# flossjtag.net
KiCad netlist of a schematic drawn in EAGLE
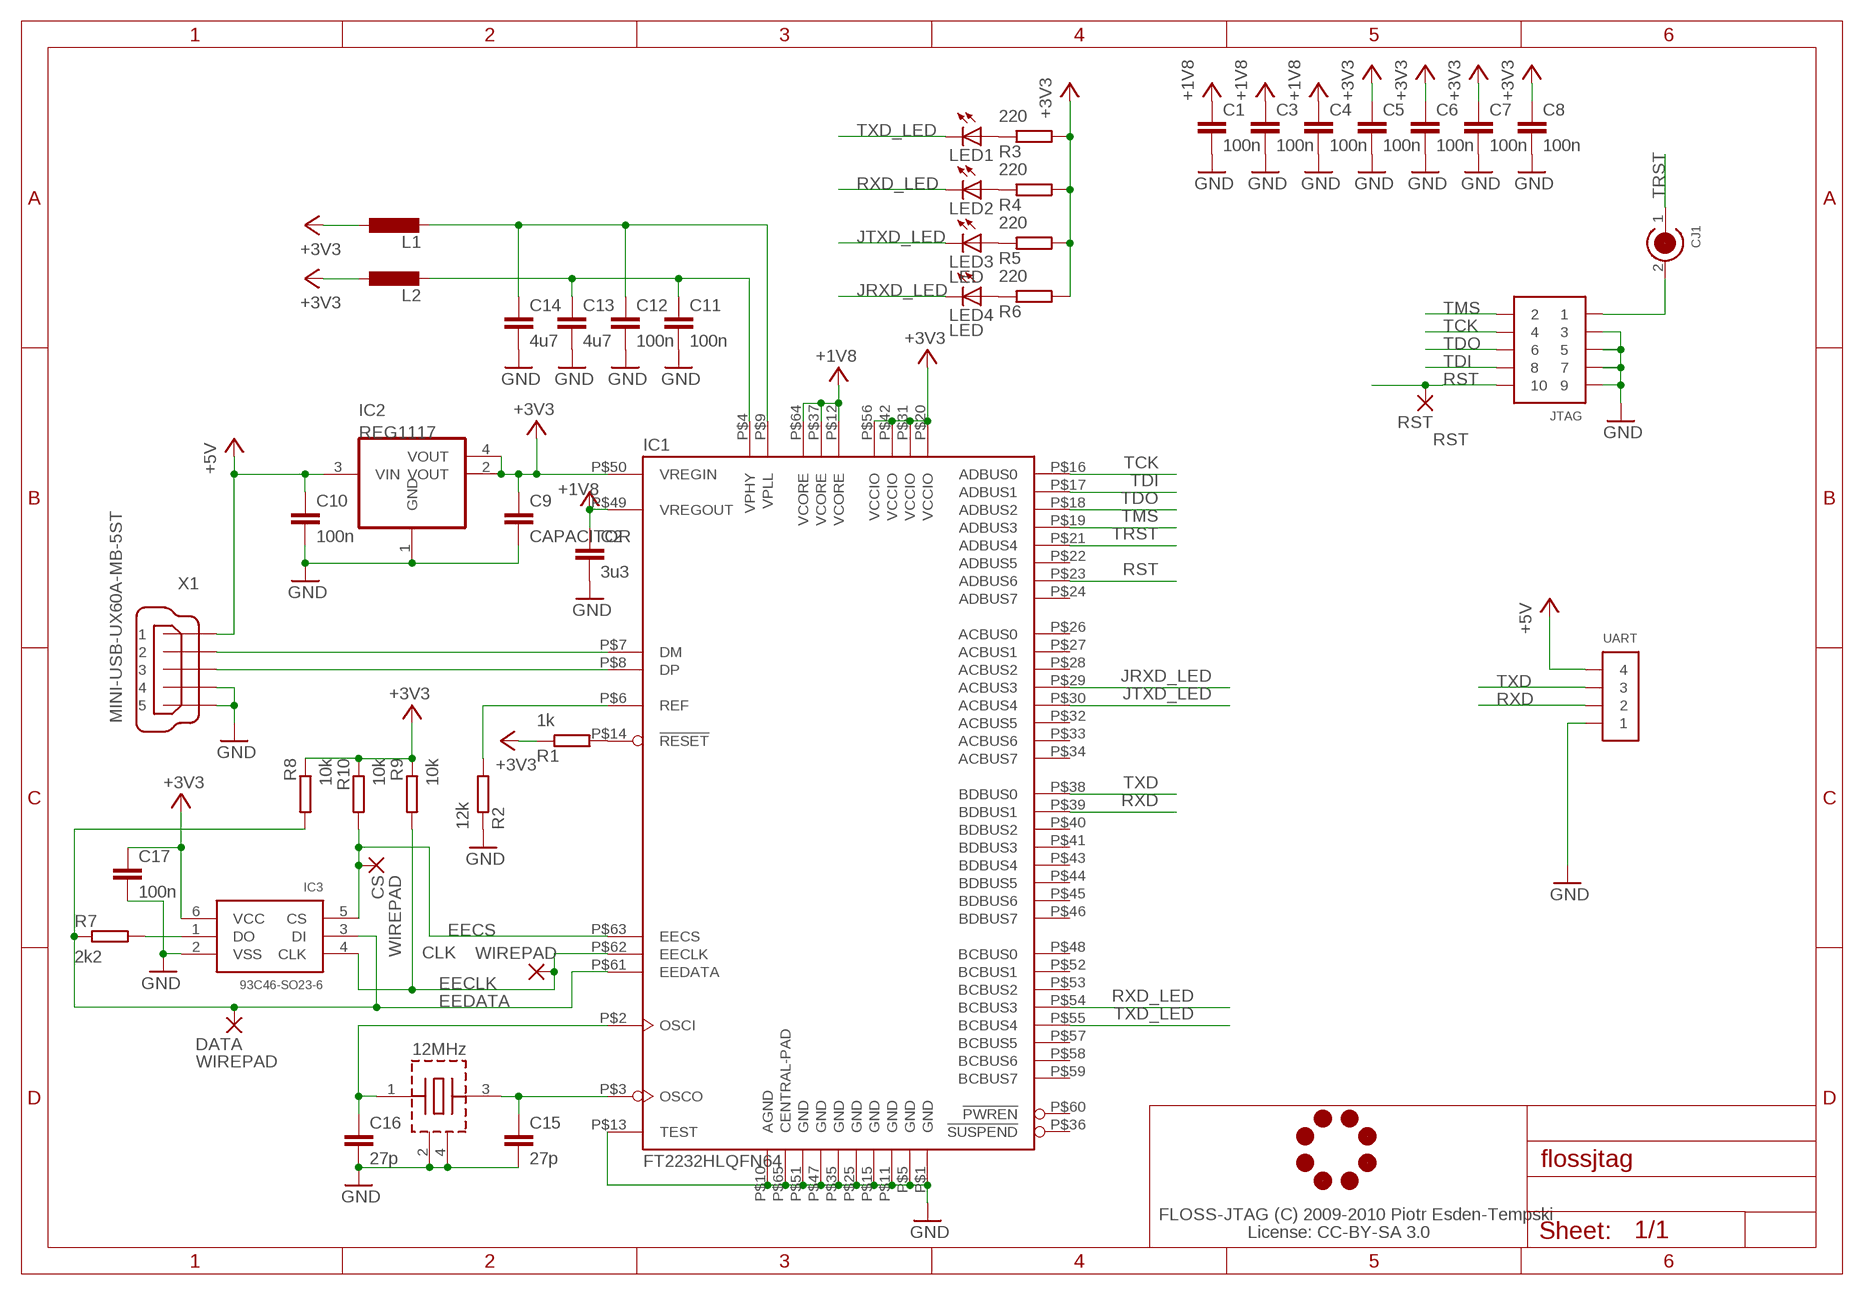
[diagram p0: schematic, sheet 1]

(export (version "E")
  (design (tool "Eeschema 10.0.6"))
  (components
    (comp (ref "C1")
      (value "100n")
      (footprint "eagle-import:0603-CAP")
      (libsource (lib "eagle-import") (part "CAPACITOR-0603"))
    )
    (comp (ref "C2")
      (value "3u3")
      (footprint "eagle-import:0603-CAP")
      (libsource (lib "eagle-import") (part "CAPACITOR-0603"))
    )
    (comp (ref "C3")
      (value "100n")
      (footprint "eagle-import:0603-CAP")
      (libsource (lib "eagle-import") (part "CAPACITOR-0603"))
    )
    (comp (ref "C4")
      (value "100n")
      (footprint "eagle-import:0603-CAP")
      (libsource (lib "eagle-import") (part "CAPACITOR-0603"))
    )
    (comp (ref "C5")
      (value "100n")
      (footprint "eagle-import:0603-CAP")
      (libsource (lib "eagle-import") (part "CAPACITOR-0603"))
    )
    (comp (ref "C6")
      (value "100n")
      (footprint "eagle-import:0603-CAP")
      (libsource (lib "eagle-import") (part "CAPACITOR-0603"))
    )
    (comp (ref "C7")
      (value "100n")
      (footprint "eagle-import:0603-CAP")
      (libsource (lib "eagle-import") (part "CAPACITOR-0603"))
    )
    (comp (ref "C8")
      (value "100n")
      (footprint "eagle-import:0603-CAP")
      (libsource (lib "eagle-import") (part "CAPACITOR-0603"))
    )
    (comp (ref "C9")
      (value "CAPACITOR")
      (footprint "eagle-import:0603-CAP")
      (libsource (lib "eagle-import") (part "CAPACITOR"))
    )
    (comp (ref "C10")
      (value "100n")
      (footprint "eagle-import:0603-CAP")
      (libsource (lib "eagle-import") (part "CAPACITOR"))
    )
    (comp (ref "C11")
      (value "100n")
      (footprint "eagle-import:0603-CAP")
      (libsource (lib "eagle-import") (part "CAPACITOR-0603"))
    )
    (comp (ref "C12")
      (value "100n")
      (footprint "eagle-import:0603-CAP")
      (libsource (lib "eagle-import") (part "CAPACITOR-0603"))
    )
    (comp (ref "C13")
      (value "4u7")
      (footprint "eagle-import:0603-CAP")
      (libsource (lib "eagle-import") (part "CAPACITOR-0603"))
    )
    (comp (ref "C14")
      (value "4u7")
      (footprint "eagle-import:0603-CAP")
      (libsource (lib "eagle-import") (part "CAPACITOR-0603"))
    )
    (comp (ref "C15")
      (value "27p")
      (footprint "eagle-import:0603-CAP")
      (libsource (lib "eagle-import") (part "CAPACITOR"))
    )
    (comp (ref "C16")
      (value "27p")
      (footprint "eagle-import:0603-CAP")
      (libsource (lib "eagle-import") (part "CAPACITOR"))
    )
    (comp (ref "C17")
      (value "100n")
      (footprint "eagle-import:0603-CAP")
      (libsource (lib "eagle-import") (part "CAPACITOR"))
    )
    (comp (ref "CJ1")
      (value "CIRC_JMP")
      (footprint "eagle-import:CIRC_JMP")
      (libsource (lib "eagle-import") (part "CIRC_JMP"))
    )
    (comp (ref "CLK")
      (value "WIREPAD")
      (footprint "eagle-import:SMD1,27")
      (libsource (lib "eagle-import") (part "WIREPAD"))
    )
    (comp (ref "CS")
      (value "WIREPAD")
      (footprint "eagle-import:SMD1,27")
      (libsource (lib "eagle-import") (part "WIREPAD"))
    )
    (comp (ref "DATA")
      (value "WIREPAD")
      (footprint "eagle-import:SMD1,27")
      (libsource (lib "eagle-import") (part "WIREPAD"))
    )
    (comp (ref "IC1")
      (value "FT2232HLQFN64")
      (footprint "eagle-import:QFN64")
      (libsource (lib "eagle-import") (part "FT2232HLQFN64"))
    )
    (comp (ref "IC2")
      (value "REG1117")
      (footprint "eagle-import:SOT223")
      (libsource (lib "eagle-import") (part "REG1117"))
    )
    (comp (ref "IC3")
      (value "93C46-SO23-6")
      (footprint "eagle-import:SO23-6")
      (libsource (lib "eagle-import") (part "93C46-SO23-6"))
    )
    (comp (ref "JL1")
      (value "JOBY_LOGO-6MIL")
      (footprint "eagle-import:JOBY_LOGO_6MIL")
      (libsource (lib "eagle-import") (part "JOBY_LOGO-6MIL"))
    )
    (comp (ref "JTAG")
      (value "CONN_5-2-FTSH-V")
      (footprint "eagle-import:FTSH-105-DV")
      (libsource (lib "eagle-import") (part "CONN_5-2-FTSH-V"))
    )
    (comp (ref "L1")
      (value "INDUCTOR-0603")
      (footprint "eagle-import:0603-IND")
      (libsource (lib "eagle-import") (part "INDUCTOR-0603"))
    )
    (comp (ref "L2")
      (value "INDUCTOR-0603")
      (footprint "eagle-import:0603-IND")
      (libsource (lib "eagle-import") (part "INDUCTOR-0603"))
    )
    (comp (ref "LED1")
      (value "LED")
      (footprint "eagle-import:0603-LED")
      (libsource (lib "eagle-import") (part "LED"))
    )
    (comp (ref "LED2")
      (value "LED")
      (footprint "eagle-import:0603-LED")
      (libsource (lib "eagle-import") (part "LED"))
    )
    (comp (ref "LED3")
      (value "LED")
      (footprint "eagle-import:0603-LED")
      (libsource (lib "eagle-import") (part "LED"))
    )
    (comp (ref "LED4")
      (value "LED")
      (footprint "eagle-import:0603-LED")
      (libsource (lib "eagle-import") (part "LED"))
    )
    (comp (ref "R1")
      (value "1k")
      (footprint "eagle-import:0603-RES")
      (libsource (lib "eagle-import") (part "RESISTOR-0603"))
    )
    (comp (ref "R2")
      (value "12k")
      (footprint "eagle-import:0603-RES")
      (libsource (lib "eagle-import") (part "RESISTOR-0603"))
    )
    (comp (ref "R3")
      (value "220")
      (footprint "eagle-import:0603-RES")
      (libsource (lib "eagle-import") (part "RESISTOR-0603"))
    )
    (comp (ref "R4")
      (value "220")
      (footprint "eagle-import:0603-RES")
      (libsource (lib "eagle-import") (part "RESISTOR-0603"))
    )
    (comp (ref "R5")
      (value "220")
      (footprint "eagle-import:0603-RES")
      (libsource (lib "eagle-import") (part "RESISTOR-0603"))
    )
    (comp (ref "R6")
      (value "220")
      (footprint "eagle-import:0603-RES")
      (libsource (lib "eagle-import") (part "RESISTOR-0603"))
    )
    (comp (ref "R7")
      (value "2k2")
      (footprint "eagle-import:0603-RES")
      (libsource (lib "eagle-import") (part "RESISTOR-0603"))
    )
    (comp (ref "R8")
      (value "10k")
      (footprint "eagle-import:0603-RES")
      (libsource (lib "eagle-import") (part "RESISTOR-0603"))
    )
    (comp (ref "R9")
      (value "10k")
      (footprint "eagle-import:0603-RES")
      (libsource (lib "eagle-import") (part "RESISTOR-0603"))
    )
    (comp (ref "R10")
      (value "10k")
      (footprint "eagle-import:0603-RES")
      (libsource (lib "eagle-import") (part "RESISTOR-0603"))
    )
    (comp (ref "RST")
      (value "RST")
      (footprint "eagle-import:SMD1,27")
      (libsource (lib "eagle-import") (part "WIREPAD"))
    )
    (comp (ref "UART")
      (value "CONN_4-1")
      (footprint "eagle-import:PB-53261-04")
      (libsource (lib "eagle-import") (part "CONN_4-1"))
    )
    (comp (ref "X1")
      (value "MINI-USB-UX60A-MB-5ST")
      (footprint "eagle-import:UX60A-MB-5ST")
      (libsource (lib "eagle-import") (part "MINI-USB-UX60A-MB-5ST"))
    )
    (comp (ref "X3")
      (value "12MHz")
      (footprint "eagle-import:NX3225SA")
      (libsource (lib "eagle-import") (part "NX3225SA"))
    )
  )
  (nets
    (net (code "1") (name "+1V8") (class "Default")
      (node (ref "C1") (pin "P$1") (pinfunction "1_P$1") (pintype "passive"))
      (node (ref "C2") (pin "P$1") (pinfunction "1_P$1") (pintype "passive"))
      (node (ref "C3") (pin "P$1") (pinfunction "1_P$1") (pintype "passive"))
      (node (ref "C4") (pin "P$1") (pinfunction "1_P$1") (pintype "passive"))
      (node (ref "IC1") (pin "P$12") (pinfunction "VCORE_P$12") (pintype "bidirectional"))
      (node (ref "IC1") (pin "P$37") (pinfunction "VCORE_P$37") (pintype "bidirectional"))
      (node (ref "IC1") (pin "P$49") (pinfunction "VREGOUT_P$49") (pintype "bidirectional"))
      (node (ref "IC1") (pin "P$64") (pinfunction "VCORE_P$64") (pintype "bidirectional"))
    )
    (net (code "2") (name "+3V3") (class "Default")
      (node (ref "C17") (pin "P$1") (pinfunction "1_P$1") (pintype "passive"))
      (node (ref "C5") (pin "P$1") (pinfunction "1_P$1") (pintype "passive"))
      (node (ref "C6") (pin "P$1") (pinfunction "1_P$1") (pintype "passive"))
      (node (ref "C7") (pin "P$1") (pinfunction "1_P$1") (pintype "passive"))
      (node (ref "C8") (pin "P$1") (pinfunction "1_P$1") (pintype "passive"))
      (node (ref "C9") (pin "P$1") (pinfunction "1_P$1") (pintype "passive"))
      (node (ref "IC1") (pin "P$20") (pinfunction "VCCIO_P$20") (pintype "bidirectional"))
      (node (ref "IC1") (pin "P$31") (pinfunction "VCCIO_P$31") (pintype "bidirectional"))
      (node (ref "IC1") (pin "P$42") (pinfunction "VCCIO_P$42") (pintype "bidirectional"))
      (node (ref "IC1") (pin "P$50") (pinfunction "VREGIN_P$50") (pintype "bidirectional"))
      (node (ref "IC1") (pin "P$56") (pinfunction "VCCIO_P$56") (pintype "bidirectional"))
      (node (ref "IC2") (pin "2") (pinfunction "VOUT_2") (pintype "output"))
      (node (ref "IC2") (pin "4") (pinfunction "VOUT_4") (pintype "output"))
      (node (ref "IC3") (pin "6") (pinfunction "VCC_6") (pintype "bidirectional"))
      (node (ref "L1") (pin "P$1") (pinfunction "1_P$1") (pintype "passive"))
      (node (ref "L2") (pin "P$1") (pinfunction "1_P$1") (pintype "passive"))
      (node (ref "R1") (pin "P$1") (pinfunction "1_P$1") (pintype "passive"))
      (node (ref "R10") (pin "P$1") (pinfunction "1_P$1") (pintype "passive"))
      (node (ref "R3") (pin "P$2") (pinfunction "2_P$2") (pintype "passive"))
      (node (ref "R4") (pin "P$2") (pinfunction "2_P$2") (pintype "passive"))
      (node (ref "R5") (pin "P$2") (pinfunction "2_P$2") (pintype "passive"))
      (node (ref "R6") (pin "P$2") (pinfunction "2_P$2") (pintype "passive"))
      (node (ref "R8") (pin "P$1") (pinfunction "1_P$1") (pintype "passive"))
      (node (ref "R9") (pin "P$1") (pinfunction "1_P$1") (pintype "passive"))
    )
    (net (code "3") (name "+5V") (class "Default")
      (node (ref "C10") (pin "P$1") (pinfunction "1_P$1") (pintype "passive"))
      (node (ref "IC2") (pin "3") (pinfunction "VIN_3") (pintype "input"))
      (node (ref "UART") (pin "4") (pinfunction "4_4") (pintype "bidirectional"))
      (node (ref "X1") (pin "1") (pinfunction "1_1") (pintype "input"))
    )
    (net (code "4") (name "/EECLK") (class "Default")
      (node (ref "CLK") (pin "1") (pinfunction "P_1") (pintype "passive"))
      (node (ref "IC1") (pin "P$62") (pinfunction "EECLK_P$62") (pintype "bidirectional"))
      (node (ref "IC3") (pin "4") (pinfunction "CLK_4") (pintype "bidirectional"))
      (node (ref "R9") (pin "P$2") (pinfunction "2_P$2") (pintype "passive"))
    )
    (net (code "5") (name "/EECS") (class "Default")
      (node (ref "CS") (pin "1") (pinfunction "P_1") (pintype "passive"))
      (node (ref "IC1") (pin "P$63") (pinfunction "EECS_P$63") (pintype "bidirectional"))
      (node (ref "IC3") (pin "5") (pinfunction "CS_5") (pintype "bidirectional"))
      (node (ref "R10") (pin "P$2") (pinfunction "2_P$2") (pintype "passive"))
    )
    (net (code "6") (name "/EEDATA") (class "Default")
      (node (ref "DATA") (pin "1") (pinfunction "P_1") (pintype "passive"))
      (node (ref "IC1") (pin "P$61") (pinfunction "EEDATA_P$61") (pintype "bidirectional"))
      (node (ref "IC3") (pin "3") (pinfunction "DI_3") (pintype "bidirectional"))
      (node (ref "R7") (pin "P$1") (pinfunction "1_P$1") (pintype "passive"))
      (node (ref "R8") (pin "P$2") (pinfunction "2_P$2") (pintype "passive"))
    )
    (net (code "7") (name "/JRXD_LED") (class "Default")
      (node (ref "IC1") (pin "P$29") (pinfunction "ACBUS3_P$29") (pintype "bidirectional"))
      (node (ref "LED4") (pin "C") (pinfunction "C_C") (pintype "passive"))
    )
    (net (code "8") (name "/JTXD_LED") (class "Default")
      (node (ref "IC1") (pin "P$30") (pinfunction "ACBUS4_P$30") (pintype "bidirectional"))
      (node (ref "LED3") (pin "C") (pinfunction "C_C") (pintype "passive"))
    )
    (net (code "9") (name "/RST") (class "Default")
      (node (ref "IC1") (pin "P$23") (pinfunction "ADBUS6_P$23") (pintype "bidirectional"))
      (node (ref "JTAG") (pin "10") (pinfunction "10_10") (pintype "bidirectional"))
      (node (ref "RST") (pin "1") (pinfunction "P_1") (pintype "passive"))
    )
    (net (code "10") (name "/RXD") (class "Default")
      (node (ref "IC1") (pin "P$39") (pinfunction "BDBUS1_P$39") (pintype "bidirectional"))
      (node (ref "UART") (pin "2") (pinfunction "2_2") (pintype "bidirectional"))
    )
    (net (code "11") (name "/RXD_LED") (class "Default")
      (node (ref "IC1") (pin "P$54") (pinfunction "BCBUS3_P$54") (pintype "bidirectional"))
      (node (ref "LED2") (pin "C") (pinfunction "C_C") (pintype "passive"))
    )
    (net (code "12") (name "/TCK") (class "Default")
      (node (ref "IC1") (pin "P$16") (pinfunction "ADBUS0_P$16") (pintype "bidirectional"))
      (node (ref "JTAG") (pin "4") (pinfunction "4_4") (pintype "bidirectional"))
    )
    (net (code "13") (name "/TDI") (class "Default")
      (node (ref "IC1") (pin "P$17") (pinfunction "ADBUS1_P$17") (pintype "bidirectional"))
      (node (ref "JTAG") (pin "8") (pinfunction "8_8") (pintype "bidirectional"))
    )
    (net (code "14") (name "/TDO") (class "Default")
      (node (ref "IC1") (pin "P$18") (pinfunction "ADBUS2_P$18") (pintype "bidirectional"))
      (node (ref "JTAG") (pin "6") (pinfunction "6_6") (pintype "bidirectional"))
    )
    (net (code "15") (name "/TMS") (class "Default")
      (node (ref "IC1") (pin "P$19") (pinfunction "ADBUS3_P$19") (pintype "bidirectional"))
      (node (ref "JTAG") (pin "2") (pinfunction "2_2") (pintype "bidirectional"))
    )
    (net (code "16") (name "/TRST") (class "Default")
      (node (ref "CJ1") (pin "1") (pinfunction "P$1_1") (pintype "bidirectional"))
      (node (ref "IC1") (pin "P$21") (pinfunction "ADBUS4_P$21") (pintype "bidirectional"))
    )
    (net (code "17") (name "/TXD") (class "Default")
      (node (ref "IC1") (pin "P$38") (pinfunction "BDBUS0_P$38") (pintype "bidirectional"))
      (node (ref "UART") (pin "3") (pinfunction "3_3") (pintype "bidirectional"))
    )
    (net (code "18") (name "/TXD_LED") (class "Default")
      (node (ref "IC1") (pin "P$55") (pinfunction "BCBUS4_P$55") (pintype "bidirectional"))
      (node (ref "LED1") (pin "C") (pinfunction "C_C") (pintype "passive"))
    )
    (net (code "19") (name "GND") (class "Default")
      (node (ref "C1") (pin "P$2") (pinfunction "2_P$2") (pintype "passive"))
      (node (ref "C10") (pin "P$2") (pinfunction "2_P$2") (pintype "passive"))
      (node (ref "C11") (pin "P$2") (pinfunction "2_P$2") (pintype "passive"))
      (node (ref "C12") (pin "P$2") (pinfunction "2_P$2") (pintype "passive"))
      (node (ref "C13") (pin "P$2") (pinfunction "2_P$2") (pintype "passive"))
      (node (ref "C14") (pin "P$2") (pinfunction "2_P$2") (pintype "passive"))
      (node (ref "C15") (pin "P$2") (pinfunction "2_P$2") (pintype "passive"))
      (node (ref "C16") (pin "P$2") (pinfunction "2_P$2") (pintype "passive"))
      (node (ref "C17") (pin "P$2") (pinfunction "2_P$2") (pintype "passive"))
      (node (ref "C2") (pin "P$2") (pinfunction "2_P$2") (pintype "passive"))
      (node (ref "C3") (pin "P$2") (pinfunction "2_P$2") (pintype "passive"))
      (node (ref "C4") (pin "P$2") (pinfunction "2_P$2") (pintype "passive"))
      (node (ref "C5") (pin "P$2") (pinfunction "2_P$2") (pintype "passive"))
      (node (ref "C6") (pin "P$2") (pinfunction "2_P$2") (pintype "passive"))
      (node (ref "C7") (pin "P$2") (pinfunction "2_P$2") (pintype "passive"))
      (node (ref "C8") (pin "P$2") (pinfunction "2_P$2") (pintype "passive"))
      (node (ref "C9") (pin "P$2") (pinfunction "2_P$2") (pintype "passive"))
      (node (ref "IC1") (pin "P$1") (pinfunction "GND_P$1") (pintype "bidirectional"))
      (node (ref "IC1") (pin "P$10") (pinfunction "AGND_P$10") (pintype "bidirectional"))
      (node (ref "IC1") (pin "P$11") (pinfunction "GND_P$11") (pintype "bidirectional"))
      (node (ref "IC1") (pin "P$13") (pinfunction "TEST_P$13") (pintype "bidirectional"))
      (node (ref "IC1") (pin "P$15") (pinfunction "GND_P$15") (pintype "bidirectional"))
      (node (ref "IC1") (pin "P$25") (pinfunction "GND_P$25") (pintype "bidirectional"))
      (node (ref "IC1") (pin "P$35") (pinfunction "GND_P$35") (pintype "bidirectional"))
      (node (ref "IC1") (pin "P$47") (pinfunction "GND_P$47") (pintype "bidirectional"))
      (node (ref "IC1") (pin "P$5") (pinfunction "GND_P$5") (pintype "bidirectional"))
      (node (ref "IC1") (pin "P$51") (pinfunction "GND_P$51") (pintype "bidirectional"))
      (node (ref "IC1") (pin "P$65") (pinfunction "CENTRAL-PAD_P$65") (pintype "bidirectional"))
      (node (ref "IC2") (pin "1") (pinfunction "GND_1") (pintype "power_in"))
      (node (ref "IC3") (pin "2") (pinfunction "VSS_2") (pintype "bidirectional"))
      (node (ref "JTAG") (pin "3") (pinfunction "3_3") (pintype "bidirectional"))
      (node (ref "JTAG") (pin "5") (pinfunction "5_5") (pintype "bidirectional"))
      (node (ref "JTAG") (pin "7") (pinfunction "7_7") (pintype "bidirectional"))
      (node (ref "JTAG") (pin "9") (pinfunction "9_9") (pintype "bidirectional"))
      (node (ref "R2") (pin "P$1") (pinfunction "1_P$1") (pintype "passive"))
      (node (ref "UART") (pin "1") (pinfunction "1_1") (pintype "bidirectional"))
      (node (ref "X1") (pin "4") (pinfunction "4_4") (pintype "input"))
      (node (ref "X1") (pin "5") (pinfunction "5_5") (pintype "input"))
      (node (ref "X3") (pin "2") (pinfunction "GND_2") (pintype "bidirectional"))
      (node (ref "X3") (pin "4") (pinfunction "GND_4") (pintype "bidirectional"))
    )
    (net (code "20") (name "Net-(C11-1)") (class "Default")
      (node (ref "C11") (pin "P$1") (pinfunction "1_P$1") (pintype "passive"))
      (node (ref "C13") (pin "P$1") (pinfunction "1_P$1") (pintype "passive"))
      (node (ref "IC1") (pin "P$4") (pinfunction "VPHY_P$4") (pintype "bidirectional"))
      (node (ref "L2") (pin "P$2") (pinfunction "2_P$2") (pintype "passive"))
    )
    (net (code "21") (name "Net-(C12-1)") (class "Default")
      (node (ref "C12") (pin "P$1") (pinfunction "1_P$1") (pintype "passive"))
      (node (ref "C14") (pin "P$1") (pinfunction "1_P$1") (pintype "passive"))
      (node (ref "IC1") (pin "P$9") (pinfunction "VPLL_P$9") (pintype "bidirectional"))
      (node (ref "L1") (pin "P$2") (pinfunction "2_P$2") (pintype "passive"))
    )
    (net (code "22") (name "Net-(C15-1)") (class "Default")
      (node (ref "C15") (pin "P$1") (pinfunction "1_P$1") (pintype "passive"))
      (node (ref "IC1") (pin "P$3") (pinfunction "OSCO_P$3") (pintype "bidirectional"))
      (node (ref "X3") (pin "3") (pinfunction "XTAL_3") (pintype "bidirectional"))
    )
    (net (code "23") (name "Net-(C16-1)") (class "Default")
      (node (ref "C16") (pin "P$1") (pinfunction "1_P$1") (pintype "passive"))
      (node (ref "IC1") (pin "P$2") (pinfunction "OSCI_P$2") (pintype "bidirectional"))
      (node (ref "X3") (pin "1") (pinfunction "XTAL_1") (pintype "bidirectional"))
    )
    (net (code "24") (name "Net-(CJ1-P$2)") (class "Default")
      (node (ref "CJ1") (pin "2") (pinfunction "P$2_2") (pintype "bidirectional"))
      (node (ref "JTAG") (pin "1") (pinfunction "1_1") (pintype "bidirectional"))
    )
    (net (code "25") (name "Net-(IC1-DM)") (class "Default")
      (node (ref "IC1") (pin "P$7") (pinfunction "DM_P$7") (pintype "bidirectional"))
      (node (ref "X1") (pin "2") (pinfunction "2_2") (pintype "input"))
    )
    (net (code "26") (name "Net-(IC1-DP)") (class "Default")
      (node (ref "IC1") (pin "P$8") (pinfunction "DP_P$8") (pintype "bidirectional"))
      (node (ref "X1") (pin "3") (pinfunction "3_3") (pintype "input"))
    )
    (net (code "27") (name "Net-(IC1-REF)") (class "Default")
      (node (ref "IC1") (pin "P$6") (pinfunction "REF_P$6") (pintype "bidirectional"))
      (node (ref "R2") (pin "P$2") (pinfunction "2_P$2") (pintype "passive"))
    )
    (net (code "28") (name "Net-(IC1-~{RESET})") (class "Default")
      (node (ref "IC1") (pin "P$14") (pinfunction "~{RESET}_P$14") (pintype "bidirectional"))
      (node (ref "R1") (pin "P$2") (pinfunction "2_P$2") (pintype "passive"))
    )
    (net (code "29") (name "Net-(IC3-DO)") (class "Default")
      (node (ref "IC3") (pin "1") (pinfunction "DO_1") (pintype "bidirectional"))
      (node (ref "R7") (pin "P$2") (pinfunction "2_P$2") (pintype "passive"))
    )
    (net (code "30") (name "Net-(R3-1)") (class "Default")
      (node (ref "LED1") (pin "A") (pinfunction "A_A") (pintype "passive"))
      (node (ref "R3") (pin "P$1") (pinfunction "1_P$1") (pintype "passive"))
    )
    (net (code "31") (name "Net-(R4-1)") (class "Default")
      (node (ref "LED2") (pin "A") (pinfunction "A_A") (pintype "passive"))
      (node (ref "R4") (pin "P$1") (pinfunction "1_P$1") (pintype "passive"))
    )
    (net (code "32") (name "Net-(R5-1)") (class "Default")
      (node (ref "LED3") (pin "A") (pinfunction "A_A") (pintype "passive"))
      (node (ref "R5") (pin "P$1") (pinfunction "1_P$1") (pintype "passive"))
    )
    (net (code "33") (name "Net-(R6-1)") (class "Default")
      (node (ref "LED4") (pin "A") (pinfunction "A_A") (pintype "passive"))
      (node (ref "R6") (pin "P$1") (pinfunction "1_P$1") (pintype "passive"))
    )
    (net (code "34") (name "unconnected-(IC1-ACBUS0-PadP$26)") (class "Default")
      (node (ref "IC1") (pin "P$26") (pinfunction "ACBUS0_P$26") (pintype "bidirectional"))
    )
    (net (code "35") (name "unconnected-(IC1-ACBUS1-PadP$27)") (class "Default")
      (node (ref "IC1") (pin "P$27") (pinfunction "ACBUS1_P$27") (pintype "bidirectional"))
    )
    (net (code "36") (name "unconnected-(IC1-ACBUS2-PadP$28)") (class "Default")
      (node (ref "IC1") (pin "P$28") (pinfunction "ACBUS2_P$28") (pintype "bidirectional"))
    )
    (net (code "37") (name "unconnected-(IC1-ACBUS5-PadP$32)") (class "Default")
      (node (ref "IC1") (pin "P$32") (pinfunction "ACBUS5_P$32") (pintype "bidirectional"))
    )
    (net (code "38") (name "unconnected-(IC1-ACBUS6-PadP$33)") (class "Default")
      (node (ref "IC1") (pin "P$33") (pinfunction "ACBUS6_P$33") (pintype "bidirectional"))
    )
    (net (code "39") (name "unconnected-(IC1-ACBUS7-PadP$34)") (class "Default")
      (node (ref "IC1") (pin "P$34") (pinfunction "ACBUS7_P$34") (pintype "bidirectional"))
    )
    (net (code "40") (name "unconnected-(IC1-ADBUS5-PadP$22)") (class "Default")
      (node (ref "IC1") (pin "P$22") (pinfunction "ADBUS5_P$22") (pintype "bidirectional"))
    )
    (net (code "41") (name "unconnected-(IC1-ADBUS7-PadP$24)") (class "Default")
      (node (ref "IC1") (pin "P$24") (pinfunction "ADBUS7_P$24") (pintype "bidirectional"))
    )
    (net (code "42") (name "unconnected-(IC1-BCBUS0-PadP$48)") (class "Default")
      (node (ref "IC1") (pin "P$48") (pinfunction "BCBUS0_P$48") (pintype "bidirectional"))
    )
    (net (code "43") (name "unconnected-(IC1-BCBUS1-PadP$52)") (class "Default")
      (node (ref "IC1") (pin "P$52") (pinfunction "BCBUS1_P$52") (pintype "bidirectional"))
    )
    (net (code "44") (name "unconnected-(IC1-BCBUS2-PadP$53)") (class "Default")
      (node (ref "IC1") (pin "P$53") (pinfunction "BCBUS2_P$53") (pintype "bidirectional"))
    )
    (net (code "45") (name "unconnected-(IC1-BCBUS5-PadP$57)") (class "Default")
      (node (ref "IC1") (pin "P$57") (pinfunction "BCBUS5_P$57") (pintype "bidirectional"))
    )
    (net (code "46") (name "unconnected-(IC1-BCBUS6-PadP$58)") (class "Default")
      (node (ref "IC1") (pin "P$58") (pinfunction "BCBUS6_P$58") (pintype "bidirectional"))
    )
    (net (code "47") (name "unconnected-(IC1-BCBUS7-PadP$59)") (class "Default")
      (node (ref "IC1") (pin "P$59") (pinfunction "BCBUS7_P$59") (pintype "bidirectional"))
    )
    (net (code "48") (name "unconnected-(IC1-BDBUS2-PadP$40)") (class "Default")
      (node (ref "IC1") (pin "P$40") (pinfunction "BDBUS2_P$40") (pintype "bidirectional"))
    )
    (net (code "49") (name "unconnected-(IC1-BDBUS3-PadP$41)") (class "Default")
      (node (ref "IC1") (pin "P$41") (pinfunction "BDBUS3_P$41") (pintype "bidirectional"))
    )
    (net (code "50") (name "unconnected-(IC1-BDBUS4-PadP$43)") (class "Default")
      (node (ref "IC1") (pin "P$43") (pinfunction "BDBUS4_P$43") (pintype "bidirectional"))
    )
    (net (code "51") (name "unconnected-(IC1-BDBUS5-PadP$44)") (class "Default")
      (node (ref "IC1") (pin "P$44") (pinfunction "BDBUS5_P$44") (pintype "bidirectional"))
    )
    (net (code "52") (name "unconnected-(IC1-BDBUS6-PadP$45)") (class "Default")
      (node (ref "IC1") (pin "P$45") (pinfunction "BDBUS6_P$45") (pintype "bidirectional"))
    )
    (net (code "53") (name "unconnected-(IC1-BDBUS7-PadP$46)") (class "Default")
      (node (ref "IC1") (pin "P$46") (pinfunction "BDBUS7_P$46") (pintype "bidirectional"))
    )
    (net (code "54") (name "unconnected-(IC1-~{PWREN}-PadP$60)") (class "Default")
      (node (ref "IC1") (pin "P$60") (pinfunction "~{PWREN}_P$60") (pintype "bidirectional"))
    )
    (net (code "55") (name "unconnected-(IC1-~{SUSPEND}-PadP$36)") (class "Default")
      (node (ref "IC1") (pin "P$36") (pinfunction "~{SUSPEND}_P$36") (pintype "bidirectional"))
    )
  )
)
